# DAC_MIC.net
KiCad netlist of a schematic drawn in Altium Designer
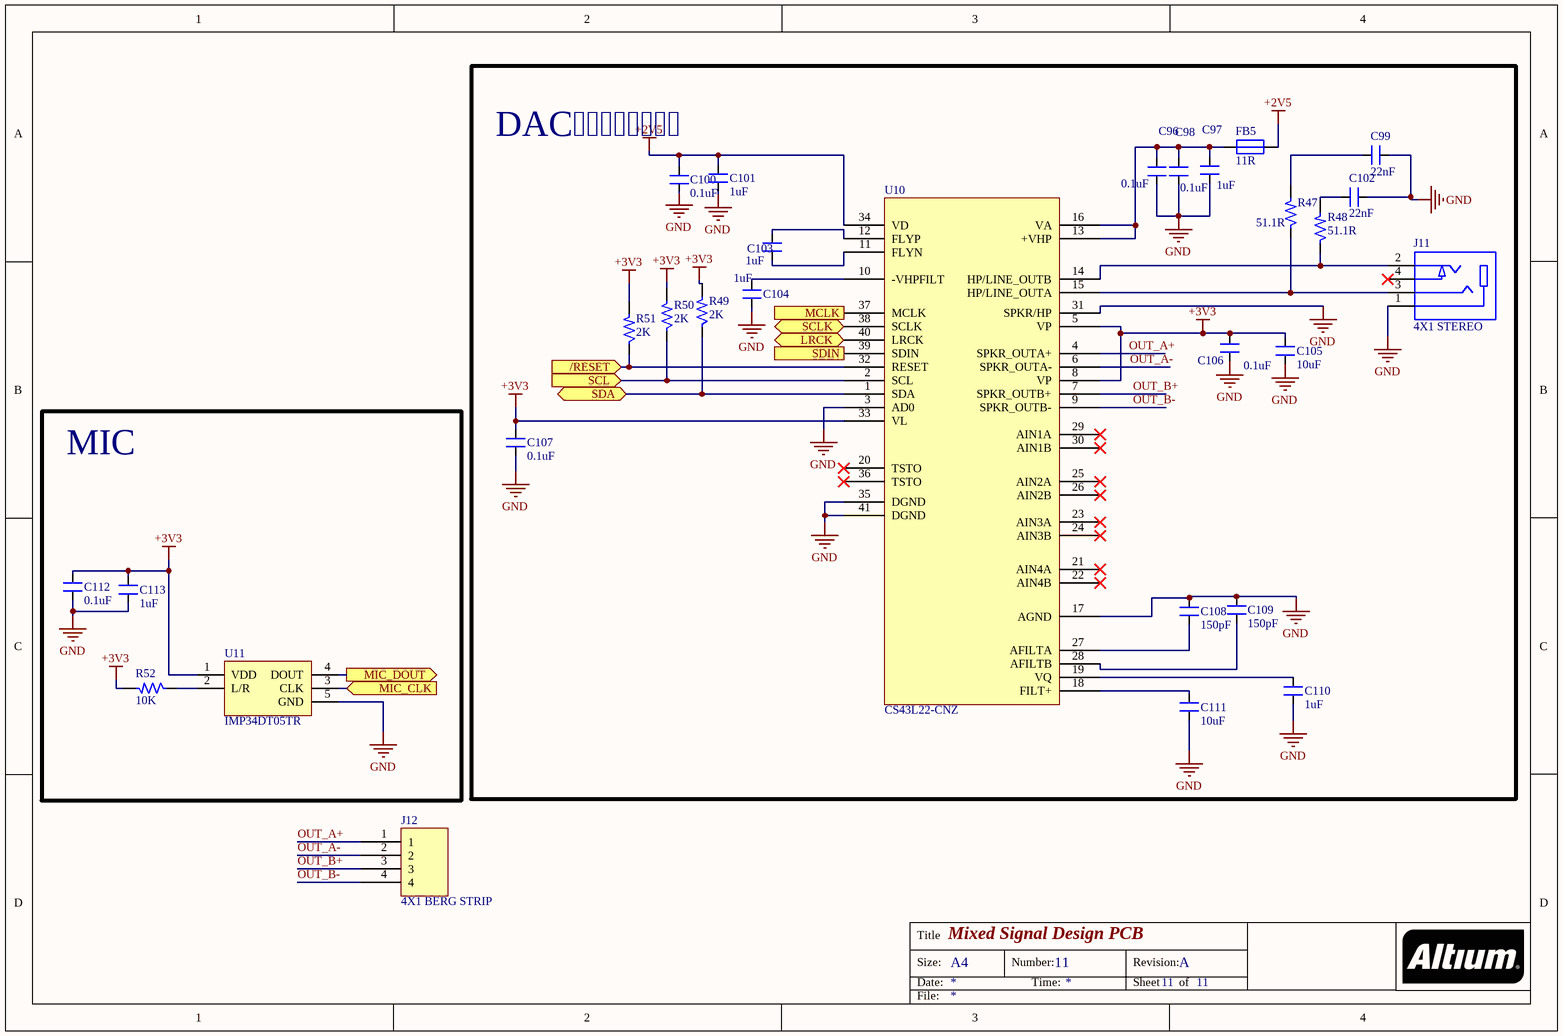
[diagram p0: DAC & MIC.SchDoc]

(export (version "E")
  (design (tool "Eeschema 10.0.6"))
  (components
    (comp (ref "C96")
      (value "0.1uF")
      (footprint "CAP_0805")
      (description "0.1µF ±5% 50V Ceramic Capacitor X7R 0805 (2012 Metric)")
      (fields
        (field (name "MANUFACTURER") "AVX Corporation")
        (field (name "MANUFACTURER PART NUMBER") "08055C104JAT4A")
      )
      (libsource (lib "ESTEEMPCBLIB") (part "CAP_0.1uF-50V-5%-0805"))
    )
    (comp (ref "C97")
      (value "1uF")
      (footprint "CAP_0805")
      (description "1µF ±5% 50V Ceramic Capacitor X7R 0805 (2012 Metric)")
      (fields
        (field (name "MANUFACTURER") "Samsung")
        (field (name "MANUFACTURER PART NUMBER") "CC0805JKX7R9BB105")
      )
      (libsource (lib "ESTEEMPCBLIB") (part "CAP_1uF-50V-5%-0805"))
    )
    (comp (ref "C98")
      (value "0.1uF")
      (footprint "CAP_0805")
      (description "0.1µF ±5% 50V Ceramic Capacitor X7R 0805 (2012 Metric)")
      (fields
        (field (name "MANUFACTURER") "AVX Corporation")
        (field (name "MANUFACTURER PART NUMBER") "08055C104JAT4A")
      )
      (libsource (lib "ESTEEMPCBLIB") (part "CAP_0.1uF-50V-5%-0805"))
    )
    (comp (ref "C99")
      (value "22nF")
      (footprint "CAP_0805")
      (description "0.022µF ±10% 50V Ceramic Capacitor X7R 0805 (2012 Metric)")
      (fields
        (field (name "MANUFACTURER") "Samsung Electro-Mechanics")
        (field (name "MANUFACTURER PART NUMBER") "CL21B223KBANNNC")
      )
      (libsource (lib "ESTEEMPCBLIB") (part "CAP_22nF-50V-10%-0805"))
    )
    (comp (ref "C100")
      (value "0.1uF")
      (footprint "CAP_0805")
      (description "0.1µF ±5% 50V Ceramic Capacitor X7R 0805 (2012 Metric)")
      (fields
        (field (name "MANUFACTURER") "AVX Corporation")
        (field (name "MANUFACTURER PART NUMBER") "08055C104JAT4A")
      )
      (libsource (lib "ESTEEMPCBLIB") (part "CAP_0.1uF-50V-5%-0805"))
    )
    (comp (ref "C101")
      (value "1uF")
      (footprint "CAP_0805")
      (description "1µF ±5% 50V Ceramic Capacitor X7R 0805 (2012 Metric)")
      (fields
        (field (name "MANUFACTURER") "Samsung")
        (field (name "MANUFACTURER PART NUMBER") "CC0805JKX7R9BB105")
      )
      (libsource (lib "ESTEEMPCBLIB") (part "CAP_1uF-50V-5%-0805"))
    )
    (comp (ref "C102")
      (value "22nF")
      (footprint "CAP_0805")
      (description "0.022µF ±10% 50V Ceramic Capacitor X7R 0805 (2012 Metric)")
      (fields
        (field (name "MANUFACTURER") "Samsung Electro-Mechanics")
        (field (name "MANUFACTURER PART NUMBER") "CL21B223KBANNNC")
      )
      (libsource (lib "ESTEEMPCBLIB") (part "CAP_22nF-50V-10%-0805"))
    )
    (comp (ref "C103")
      (value "1uF")
      (footprint "CAP_0805")
      (description "1µF ±5% 50V Ceramic Capacitor X7R 0805 (2012 Metric)")
      (fields
        (field (name "MANUFACTURER") "Samsung")
        (field (name "MANUFACTURER PART NUMBER") "CC0805JKX7R9BB105")
      )
      (libsource (lib "ESTEEMPCBLIB") (part "CAP_1uF-50V-5%-0805"))
    )
    (comp (ref "C104")
      (value "1uF")
      (footprint "CAP_0805")
      (description "1µF ±5% 50V Ceramic Capacitor X7R 0805 (2012 Metric)")
      (fields
        (field (name "MANUFACTURER") "Samsung")
        (field (name "MANUFACTURER PART NUMBER") "CC0805JKX7R9BB105")
      )
      (libsource (lib "ESTEEMPCBLIB") (part "CAP_1uF-50V-5%-0805"))
    )
    (comp (ref "C105")
      (value "10uF")
      (footprint "CAP_1206")
      (description "10µF ±10% 50V Ceramic Capacitor X7R 1206 (3216 Metric)")
      (fields
        (field (name "MANUFACTURER") "KEMET")
        (field (name "MANUFACTURER PART NUMBER") "CL31B106KBHNNNE")
      )
      (libsource (lib "ESTEEMPCBLIB") (part "CAP_10uF-50V-10%-1206"))
    )
    (comp (ref "C106")
      (value "0.1uF")
      (footprint "CAP_0805")
      (description "0.1µF ±5% 50V Ceramic Capacitor X7R 0805 (2012 Metric)")
      (fields
        (field (name "MANUFACTURER") "AVX Corporation")
        (field (name "MANUFACTURER PART NUMBER") "08055C104JAT4A")
      )
      (libsource (lib "ESTEEMPCBLIB") (part "CAP_0.1uF-50V-5%-0805"))
    )
    (comp (ref "C107")
      (value "0.1uF")
      (footprint "CAP_0805")
      (description "0.1µF ±5% 50V Ceramic Capacitor X7R 0805 (2012 Metric)")
      (fields
        (field (name "MANUFACTURER") "AVX Corporation")
        (field (name "MANUFACTURER PART NUMBER") "08055C104JAT4A")
      )
      (libsource (lib "ESTEEMPCBLIB") (part "CAP_0.1uF-50V-5%-0805"))
    )
    (comp (ref "C108")
      (value "150pF")
      (footprint "CAP_0805")
      (description "150pF ±10% 50V Ceramic Capacitor C0G, NP0 0805 (2012 Metric)")
      (fields
        (field (name "MANUFACTURER") "AVX Corporation")
        (field (name "MANUFACTURER PART NUMBER") "08055A151KAT2A")
      )
      (libsource (lib "ESTEEMPCBLIB") (part "CAP_150pF-50V-10%-0805"))
    )
    (comp (ref "C109")
      (value "150pF")
      (footprint "CAP_0805")
      (description "150pF ±10% 50V Ceramic Capacitor C0G, NP0 0805 (2012 Metric)")
      (fields
        (field (name "MANUFACTURER") "AVX Corporation")
        (field (name "MANUFACTURER PART NUMBER") "08055A151KAT2A")
      )
      (libsource (lib "ESTEEMPCBLIB") (part "CAP_150pF-50V-10%-0805"))
    )
    (comp (ref "C110")
      (value "1uF")
      (footprint "CAP_0805")
      (description "1µF ±5% 50V Ceramic Capacitor X7R 0805 (2012 Metric)")
      (fields
        (field (name "MANUFACTURER") "Samsung")
        (field (name "MANUFACTURER PART NUMBER") "CC0805JKX7R9BB105")
      )
      (libsource (lib "ESTEEMPCBLIB") (part "CAP_1uF-50V-5%-0805"))
    )
    (comp (ref "C111")
      (value "10uF")
      (footprint "CAP_1206")
      (description "10µF ±10% 50V Ceramic Capacitor X7R 1206 (3216 Metric)")
      (fields
        (field (name "MANUFACTURER") "KEMET")
        (field (name "MANUFACTURER PART NUMBER") "CL31B106KBHNNNE")
      )
      (libsource (lib "ESTEEMPCBLIB") (part "CAP_10uF-50V-10%-1206"))
    )
    (comp (ref "C112")
      (value "0.1uF")
      (footprint "CAP_0805")
      (description "0.1µF ±5% 50V Ceramic Capacitor X7R 0805 (2012 Metric)")
      (fields
        (field (name "MANUFACTURER") "AVX Corporation")
        (field (name "MANUFACTURER PART NUMBER") "08055C104JAT4A")
      )
      (libsource (lib "ESTEEMPCBLIB") (part "CAP_0.1uF-50V-5%-0805"))
    )
    (comp (ref "C113")
      (value "1uF")
      (footprint "CAP_0805")
      (description "1µF ±5% 50V Ceramic Capacitor X7R 0805 (2012 Metric)")
      (fields
        (field (name "MANUFACTURER") "Samsung")
        (field (name "MANUFACTURER PART NUMBER") "CC0805JKX7R9BB105")
      )
      (libsource (lib "ESTEEMPCBLIB") (part "CAP_1uF-50V-5%-0805"))
    )
    (comp (ref "FB5")
      (value "11R")
      (footprint "IND_0805")
      (description "11 Ohms @ 100MHz 1 Power Line Ferrite Bead 0805 (2012 Metric) 1.5A 60mOhm")
      (fields
        (field (name "MANUFACTURER") "Murata")
        (field (name "MANUFACTURER PART NUMBER") "MI0805K110R-10")
      )
      (libsource (lib "ESTEEMPCBLIB") (part "FB_11R-100MHZ-1.5A-0805"))
    )
    (comp (ref "J11")
      (value "4X1 STEREO")
      (footprint "CON_SJ-2504A-SMT-TR_SMD")
      (fields
        (field (name "MANUFACTURER") "CUI Devices")
        (field (name "MANUFACTURER PART NUMBER") "SJ-2504A-SMT-TR")
      )
      (libsource (lib "ESTEEMPCBLIB") (part "CON-PLG-STEREO_4X1-100-RA-SMD"))
    )
    (comp (ref "J12")
      (value "4X1 BERG STRIP")
      (footprint "CON4_100_40D72_TH_ST_MALE")
      (description "4 Pins, 1 Row 2.54mm Pitch, Straight bergstrip, Male")
      (fields (field (name "MANUFACTURER") "NA"))
      (libsource (lib "ESTEEMPCBLIB") (part "CON-BS-PLG_4X1-100-ST-TH"))
    )
    (comp (ref "R47")
      (value "51.1R")
      (footprint "RES_0603")
      (description "51.1 Ohms ±1% 0.1W, 1/10W Chip Resistor 0603 (1608 Metric) Thick Film")
      (fields
        (field (name "MANUFACTURER") "Vishay Dale")
        (field (name "MANUFACTURER PART NUMBER") "CRCW060351R1FKEAC")
      )
      (libsource (lib "ESTEEMPCBLIB") (part "RES_51.1R-0.1W-1%-0603"))
    )
    (comp (ref "R48")
      (value "51.1R")
      (footprint "RES_0603")
      (description "51.1 Ohms ±1% 0.1W, 1/10W Chip Resistor 0603 (1608 Metric) Thick Film")
      (fields
        (field (name "MANUFACTURER") "Vishay Dale")
        (field (name "MANUFACTURER PART NUMBER") "CRCW060351R1FKEAC")
      )
      (libsource (lib "ESTEEMPCBLIB") (part "RES_51.1R-0.1W-1%-0603"))
    )
    (comp (ref "R49")
      (value "2K")
      (footprint "RES_0805")
      (description "2 kOhms ±1% 0.125W, 1/8W Chip Resistor 0805 (2012 Metric) Moisture Resistant Thick Film")
      (fields
        (field (name "MANUFACTURER") "TE Connectivity")
        (field (name "MANUFACTURER PART NUMBER") "RC0805FR-072KL")
      )
      (libsource (lib "ESTEEMPCBLIB") (part "RES_2K-0.125W-1%-0805"))
    )
    (comp (ref "R50")
      (value "2K")
      (footprint "RES_0805")
      (description "2 kOhms ±1% 0.125W, 1/8W Chip Resistor 0805 (2012 Metric) Moisture Resistant Thick Film")
      (fields
        (field (name "MANUFACTURER") "TE Connectivity")
        (field (name "MANUFACTURER PART NUMBER") "RC0805FR-072KL")
      )
      (libsource (lib "ESTEEMPCBLIB") (part "RES_2K-0.125W-1%-0805"))
    )
    (comp (ref "R51")
      (value "2K")
      (footprint "RES_0805")
      (description "2 kOhms ±1% 0.125W, 1/8W Chip Resistor 0805 (2012 Metric) Moisture Resistant Thick Film")
      (fields
        (field (name "MANUFACTURER") "TE Connectivity")
        (field (name "MANUFACTURER PART NUMBER") "RC0805FR-072KL")
      )
      (libsource (lib "ESTEEMPCBLIB") (part "RES_2K-0.125W-1%-0805"))
    )
    (comp (ref "R52")
      (value "10K")
      (footprint "RES_0805")
      (description "10 kOhms ±1% 0.125W, 1/8W Chip Resistor 0805 (2012 Metric) Automotive AEC-Q200 Thick Film")
      (fields (field (name "MANUFACTURER") "CTS") (field (name "MANUFACTURER PART NUMBER") "WR08X1002FTL"))
      (libsource (lib "ESTEEMPCBLIB") (part "RES_10K-0.125W-1%-0805"))
    )
    (comp (ref "U10")
      (value "CS43L22-CNZ")
      (footprint "QFN40_19_284_33X9_SMD")
      (description "Audio D/A Converter ICs Low Power Stereo DAC w/ClassD Spkr Driver")
      (fields (field (name "MANUFACTURER") "Cirrus Logic"))
      (libsource (lib "ESTEEMPCBLIB") (part "IC_CS43L22"))
    )
    (comp (ref "U11")
      (value "IMP34DT05TR")
      (footprint "HCLGA-4_53_137_15X37_SMD")
      (description "MEMS Microphones AUTO & INDUSTRIAL SENSORS")
      (fields (field (name "MANUFACTURER") "STMicroelectronics"))
      (libsource (lib "ESTEEMPCBLIB") (part "IC_IMP34DT05TR"))
    )
  )
  (nets
    (net (code "1") (name "+2V5") (class "Default")
      (node (ref "C100") (pin "1") (pinfunction "1_1") (pintype "passive"))
      (node (ref "C101") (pin "2") (pinfunction "2_2") (pintype "passive"))
      (node (ref "FB5") (pin "2") (pinfunction "2_2") (pintype "passive"))
      (node (ref "U10") (pin "34") (pinfunction "VD_34") (pintype "passive"))
    )
    (net (code "2") (name "+3V3") (class "Default")
      (node (ref "C105") (pin "2") (pinfunction "2_2") (pintype "passive"))
      (node (ref "C106") (pin "1") (pinfunction "1_1") (pintype "passive"))
      (node (ref "C107") (pin "1") (pinfunction "1_1") (pintype "passive"))
      (node (ref "C112") (pin "1") (pinfunction "1_1") (pintype "passive"))
      (node (ref "C113") (pin "2") (pinfunction "2_2") (pintype "passive"))
      (node (ref "R49") (pin "2") (pinfunction "2_2") (pintype "passive"))
      (node (ref "R50") (pin "2") (pinfunction "2_2") (pintype "passive"))
      (node (ref "R51") (pin "2") (pinfunction "2_2") (pintype "passive"))
      (node (ref "R52") (pin "2") (pinfunction "2_2") (pintype "passive"))
      (node (ref "U10") (pin "33") (pinfunction "VL_33") (pintype "passive"))
      (node (ref "U10") (pin "5") (pinfunction "VP_5") (pintype "passive"))
      (node (ref "U10") (pin "8") (pinfunction "VP_8") (pintype "passive"))
      (node (ref "U11") (pin "1") (pinfunction "VDD_1") (pintype "passive"))
    )
    (net (code "3") (name "/LRCK") (class "Default")
      (node (ref "U10") (pin "40") (pinfunction "LRCK_40") (pintype "passive"))
    )
    (net (code "4") (name "/MCLK") (class "Default")
      (node (ref "U10") (pin "37") (pinfunction "MCLK_37") (pintype "passive"))
    )
    (net (code "5") (name "/MIC_CLK") (class "Default")
      (node (ref "U11") (pin "3") (pinfunction "CLK_3") (pintype "passive"))
    )
    (net (code "6") (name "/MIC_DOUT") (class "Default")
      (node (ref "U11") (pin "4") (pinfunction "DOUT_4") (pintype "passive"))
    )
    (net (code "7") (name "/OUT_A+") (class "Default")
      (node (ref "J12") (pin "1") (pinfunction "1_1") (pintype "passive"))
      (node (ref "U10") (pin "4") (pinfunction "SPKR_OUTA+_4") (pintype "passive"))
    )
    (net (code "8") (name "/OUT_A-") (class "Default")
      (node (ref "J12") (pin "2") (pinfunction "2_2") (pintype "passive"))
      (node (ref "U10") (pin "6") (pinfunction "SPKR_OUTA-_6") (pintype "passive"))
    )
    (net (code "9") (name "/OUT_B+") (class "Default")
      (node (ref "J12") (pin "3") (pinfunction "3_3") (pintype "passive"))
      (node (ref "U10") (pin "7") (pinfunction "SPKR_OUTB+_7") (pintype "passive"))
    )
    (net (code "10") (name "/OUT_B-") (class "Default")
      (node (ref "J12") (pin "4") (pinfunction "4_4") (pintype "passive"))
      (node (ref "U10") (pin "9") (pinfunction "SPKR_OUTB-_9") (pintype "passive"))
    )
    (net (code "11") (name "/SCL") (class "Default")
      (node (ref "R50") (pin "1") (pinfunction "1_1") (pintype "passive"))
      (node (ref "U10") (pin "2") (pinfunction "SCL_2") (pintype "passive"))
    )
    (net (code "12") (name "/SCLK") (class "Default")
      (node (ref "U10") (pin "38") (pinfunction "SCLK_38") (pintype "passive"))
    )
    (net (code "13") (name "/SDA") (class "Default")
      (node (ref "R49") (pin "1") (pinfunction "1_1") (pintype "passive"))
      (node (ref "U10") (pin "1") (pinfunction "SDA_1") (pintype "passive"))
    )
    (net (code "14") (name "/SDIN") (class "Default")
      (node (ref "U10") (pin "39") (pinfunction "SDIN_39") (pintype "passive"))
    )
    (net (code "15") (name "/{slash}RESET") (class "Default")
      (node (ref "R51") (pin "1") (pinfunction "1_1") (pintype "passive"))
      (node (ref "U10") (pin "32") (pinfunction "RESET_32") (pintype "passive"))
    )
    (net (code "16") (name "GND") (class "Default")
      (node (ref "C100") (pin "2") (pinfunction "2_2") (pintype "passive"))
      (node (ref "C101") (pin "1") (pinfunction "1_1") (pintype "passive"))
      (node (ref "C102") (pin "1") (pinfunction "1_1") (pintype "passive"))
      (node (ref "C104") (pin "1") (pinfunction "1_1") (pintype "passive"))
      (node (ref "C105") (pin "1") (pinfunction "1_1") (pintype "passive"))
      (node (ref "C106") (pin "2") (pinfunction "2_2") (pintype "passive"))
      (node (ref "C107") (pin "2") (pinfunction "2_2") (pintype "passive"))
      (node (ref "C108") (pin "2") (pinfunction "2_2") (pintype "passive"))
      (node (ref "C109") (pin "2") (pinfunction "2_2") (pintype "passive"))
      (node (ref "C110") (pin "1") (pinfunction "1_1") (pintype "passive"))
      (node (ref "C111") (pin "1") (pinfunction "1_1") (pintype "passive"))
      (node (ref "C112") (pin "2") (pinfunction "2_2") (pintype "passive"))
      (node (ref "C113") (pin "1") (pinfunction "1_1") (pintype "passive"))
      (node (ref "C96") (pin "2") (pinfunction "2_2") (pintype "passive"))
      (node (ref "C97") (pin "1") (pinfunction "1_1") (pintype "passive"))
      (node (ref "C98") (pin "2") (pinfunction "2_2") (pintype "passive"))
      (node (ref "C99") (pin "1") (pinfunction "1_1") (pintype "passive"))
      (node (ref "J11") (pin "1") (pinfunction "1_1") (pintype "passive"))
      (node (ref "U10") (pin "17") (pinfunction "AGND_17") (pintype "passive"))
      (node (ref "U10") (pin "3") (pinfunction "AD0_3") (pintype "passive"))
      (node (ref "U10") (pin "31") (pinfunction "SPKR/HP_31") (pintype "passive"))
      (node (ref "U10") (pin "35") (pinfunction "DGND_35") (pintype "passive"))
      (node (ref "U10") (pin "41") (pinfunction "DGND_41") (pintype "passive"))
      (node (ref "U11") (pin "5") (pinfunction "GND_5") (pintype "passive"))
    )
    (net (code "17") (name "Net-(C99-Pad2)") (class "Default")
      (node (ref "C99") (pin "2") (pinfunction "2_2") (pintype "passive"))
      (node (ref "R47") (pin "2") (pinfunction "2_2") (pintype "passive"))
    )
    (net (code "18") (name "Net-(C102-Pad2)") (class "Default")
      (node (ref "C102") (pin "2") (pinfunction "2_2") (pintype "passive"))
      (node (ref "R48") (pin "2") (pinfunction "2_2") (pintype "passive"))
    )
    (net (code "19") (name "Net-(U10-+VHP)") (class "Default")
      (node (ref "C96") (pin "1") (pinfunction "1_1") (pintype "passive"))
      (node (ref "C97") (pin "2") (pinfunction "2_2") (pintype "passive"))
      (node (ref "C98") (pin "1") (pinfunction "1_1") (pintype "passive"))
      (node (ref "FB5") (pin "1") (pinfunction "1_1") (pintype "passive"))
      (node (ref "U10") (pin "13") (pinfunction "+VHP_13") (pintype "passive"))
      (node (ref "U10") (pin "16") (pinfunction "VA_16") (pintype "passive"))
    )
    (net (code "20") (name "Net-(U10--VHPFILT)") (class "Default")
      (node (ref "C104") (pin "2") (pinfunction "2_2") (pintype "passive"))
      (node (ref "U10") (pin "10") (pinfunction "-VHPFILT_10") (pintype "passive"))
    )
    (net (code "21") (name "Net-(U10-AFILTA)") (class "Default")
      (node (ref "C108") (pin "1") (pinfunction "1_1") (pintype "passive"))
      (node (ref "U10") (pin "27") (pinfunction "AFILTA_27") (pintype "passive"))
    )
    (net (code "22") (name "Net-(U10-AFILTB)") (class "Default")
      (node (ref "C109") (pin "1") (pinfunction "1_1") (pintype "passive"))
      (node (ref "U10") (pin "28") (pinfunction "AFILTB_28") (pintype "passive"))
    )
    (net (code "23") (name "Net-(U10-FILT+)") (class "Default")
      (node (ref "C111") (pin "2") (pinfunction "2_2") (pintype "passive"))
      (node (ref "U10") (pin "18") (pinfunction "FILT+_18") (pintype "passive"))
    )
    (net (code "24") (name "Net-(U10-FLYN)") (class "Default")
      (node (ref "C103") (pin "1") (pinfunction "1_1") (pintype "passive"))
      (node (ref "U10") (pin "11") (pinfunction "FLYN_11") (pintype "passive"))
    )
    (net (code "25") (name "Net-(U10-FLYP)") (class "Default")
      (node (ref "C103") (pin "2") (pinfunction "2_2") (pintype "passive"))
      (node (ref "U10") (pin "12") (pinfunction "FLYP_12") (pintype "passive"))
    )
    (net (code "26") (name "Net-(U10-HP{slash}LINE_OUTA)") (class "Default")
      (node (ref "J11") (pin "3") (pinfunction "3_3") (pintype "passive"))
      (node (ref "R47") (pin "1") (pinfunction "1_1") (pintype "passive"))
      (node (ref "U10") (pin "15") (pinfunction "HP/LINE_OUTA_15") (pintype "passive"))
    )
    (net (code "27") (name "Net-(U10-HP{slash}LINE_OUTB)") (class "Default")
      (node (ref "J11") (pin "2") (pinfunction "2_2") (pintype "passive"))
      (node (ref "R48") (pin "1") (pinfunction "1_1") (pintype "passive"))
      (node (ref "U10") (pin "14") (pinfunction "HP/LINE_OUTB_14") (pintype "passive"))
    )
    (net (code "28") (name "Net-(U10-VQ)") (class "Default")
      (node (ref "C110") (pin "2") (pinfunction "2_2") (pintype "passive"))
      (node (ref "U10") (pin "19") (pinfunction "VQ_19") (pintype "passive"))
    )
    (net (code "29") (name "Net-(U11-L{slash}R)") (class "Default")
      (node (ref "R52") (pin "1") (pinfunction "1_1") (pintype "passive"))
      (node (ref "U11") (pin "2") (pinfunction "L/R_2") (pintype "passive"))
    )
    (net (code "30") (name "unconnected-(J11-Pad4)") (class "Default")
      (node (ref "J11") (pin "4") (pinfunction "4_4") (pintype "passive+no_connect"))
    )
    (net (code "31") (name "unconnected-(U10-AIN1A-Pad29)") (class "Default")
      (node (ref "U10") (pin "29") (pinfunction "AIN1A_29") (pintype "passive+no_connect"))
    )
    (net (code "32") (name "unconnected-(U10-AIN1B-Pad30)") (class "Default")
      (node (ref "U10") (pin "30") (pinfunction "AIN1B_30") (pintype "passive+no_connect"))
    )
    (net (code "33") (name "unconnected-(U10-AIN2A-Pad25)") (class "Default")
      (node (ref "U10") (pin "25") (pinfunction "AIN2A_25") (pintype "passive+no_connect"))
    )
    (net (code "34") (name "unconnected-(U10-AIN2B-Pad26)") (class "Default")
      (node (ref "U10") (pin "26") (pinfunction "AIN2B_26") (pintype "passive+no_connect"))
    )
    (net (code "35") (name "unconnected-(U10-AIN3A-Pad23)") (class "Default")
      (node (ref "U10") (pin "23") (pinfunction "AIN3A_23") (pintype "passive+no_connect"))
    )
    (net (code "36") (name "unconnected-(U10-AIN3B-Pad24)") (class "Default")
      (node (ref "U10") (pin "24") (pinfunction "AIN3B_24") (pintype "passive+no_connect"))
    )
    (net (code "37") (name "unconnected-(U10-AIN4A-Pad21)") (class "Default")
      (node (ref "U10") (pin "21") (pinfunction "AIN4A_21") (pintype "passive+no_connect"))
    )
    (net (code "38") (name "unconnected-(U10-AIN4B-Pad22)") (class "Default")
      (node (ref "U10") (pin "22") (pinfunction "AIN4B_22") (pintype "passive+no_connect"))
    )
    (net (code "39") (name "unconnected-(U10-TSTO-Pad20)") (class "Default")
      (node (ref "U10") (pin "20") (pinfunction "TSTO_20") (pintype "passive+no_connect"))
    )
    (net (code "40") (name "unconnected-(U10-TSTO-Pad36)") (class "Default")
      (node (ref "U10") (pin "36") (pinfunction "TSTO_36") (pintype "passive+no_connect"))
    )
  )
)
